# auxDaqUnitBottom2022.net
KiCad netlist of a schematic drawn in EAGLE
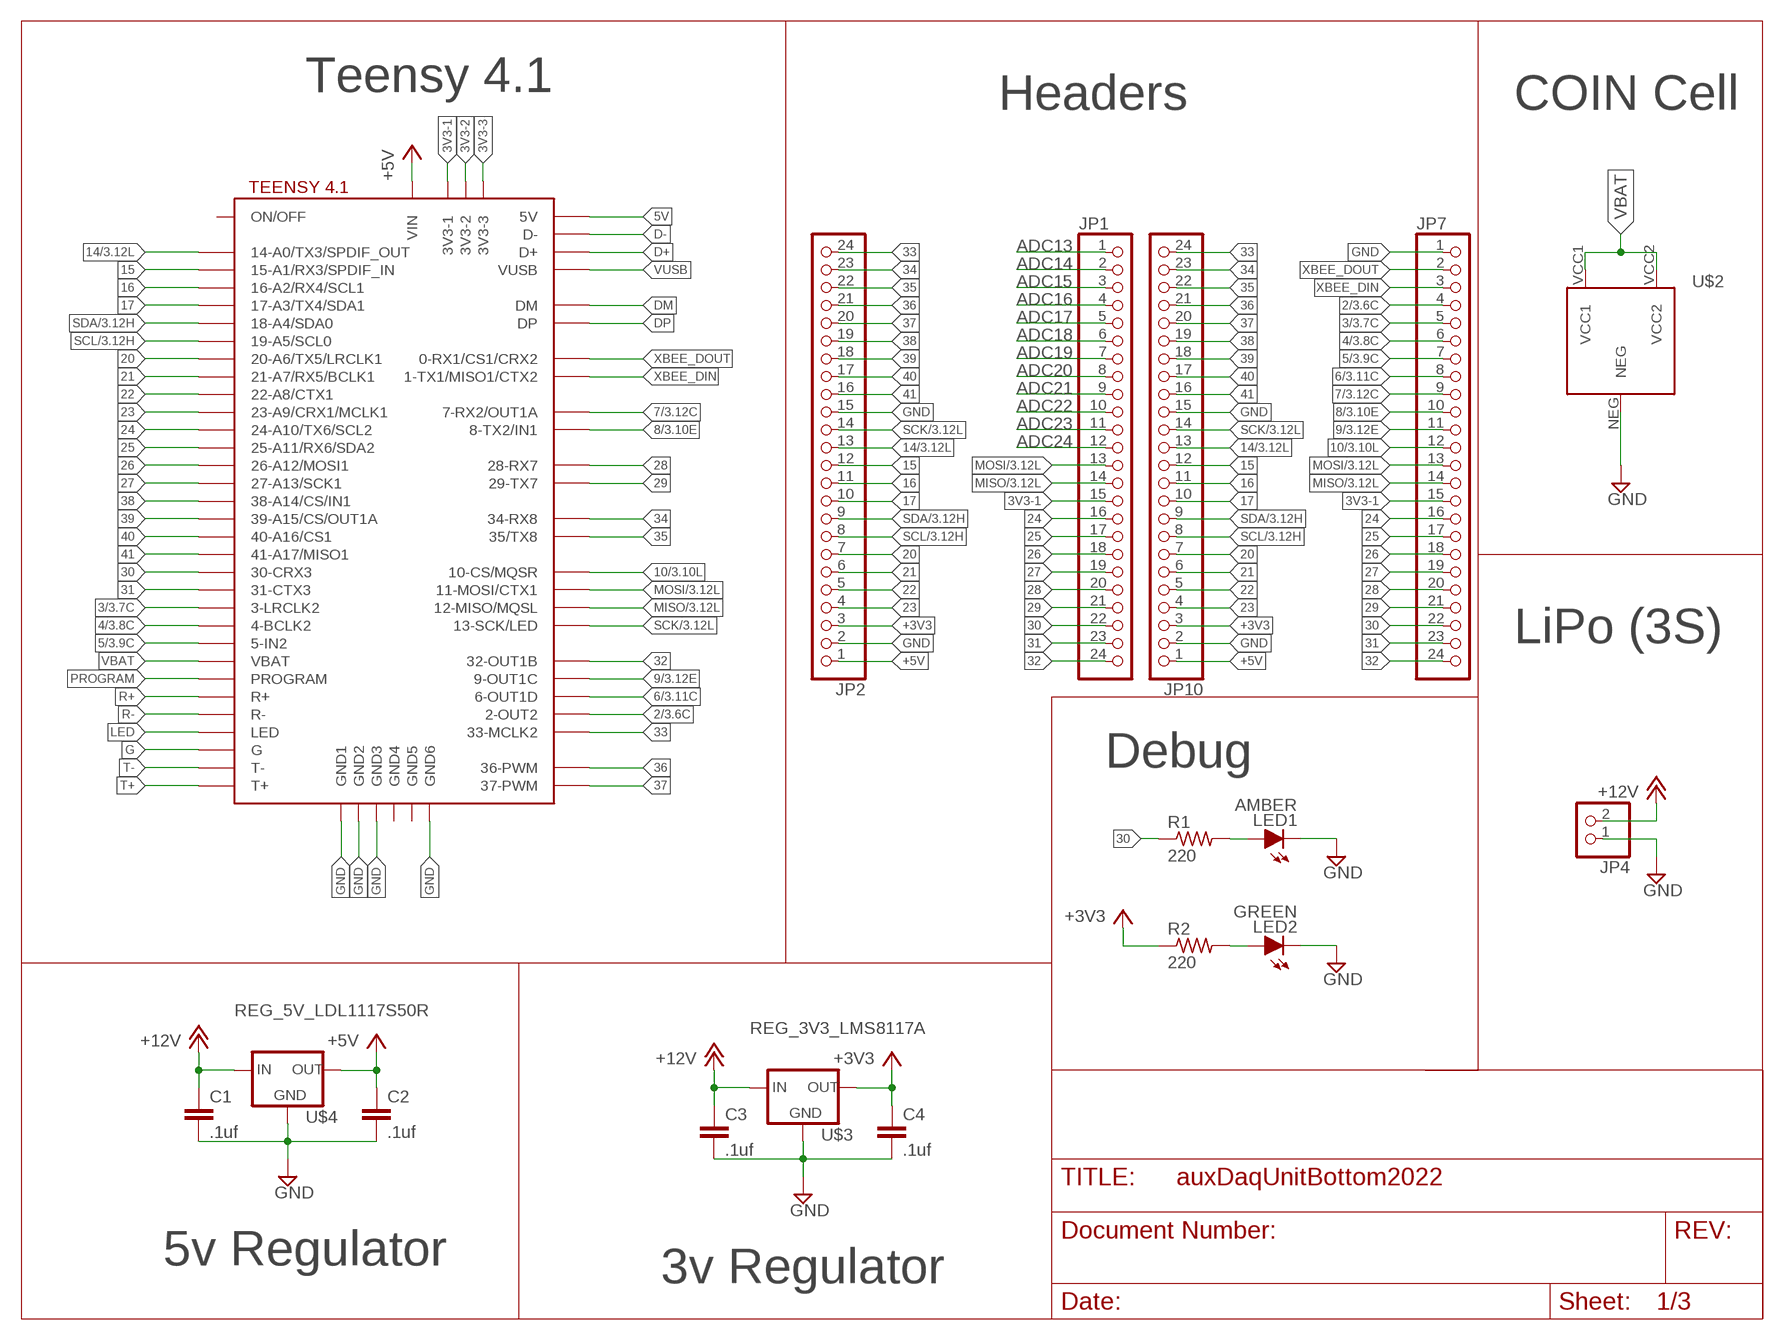
[diagram p0: schematic, sheet 1]
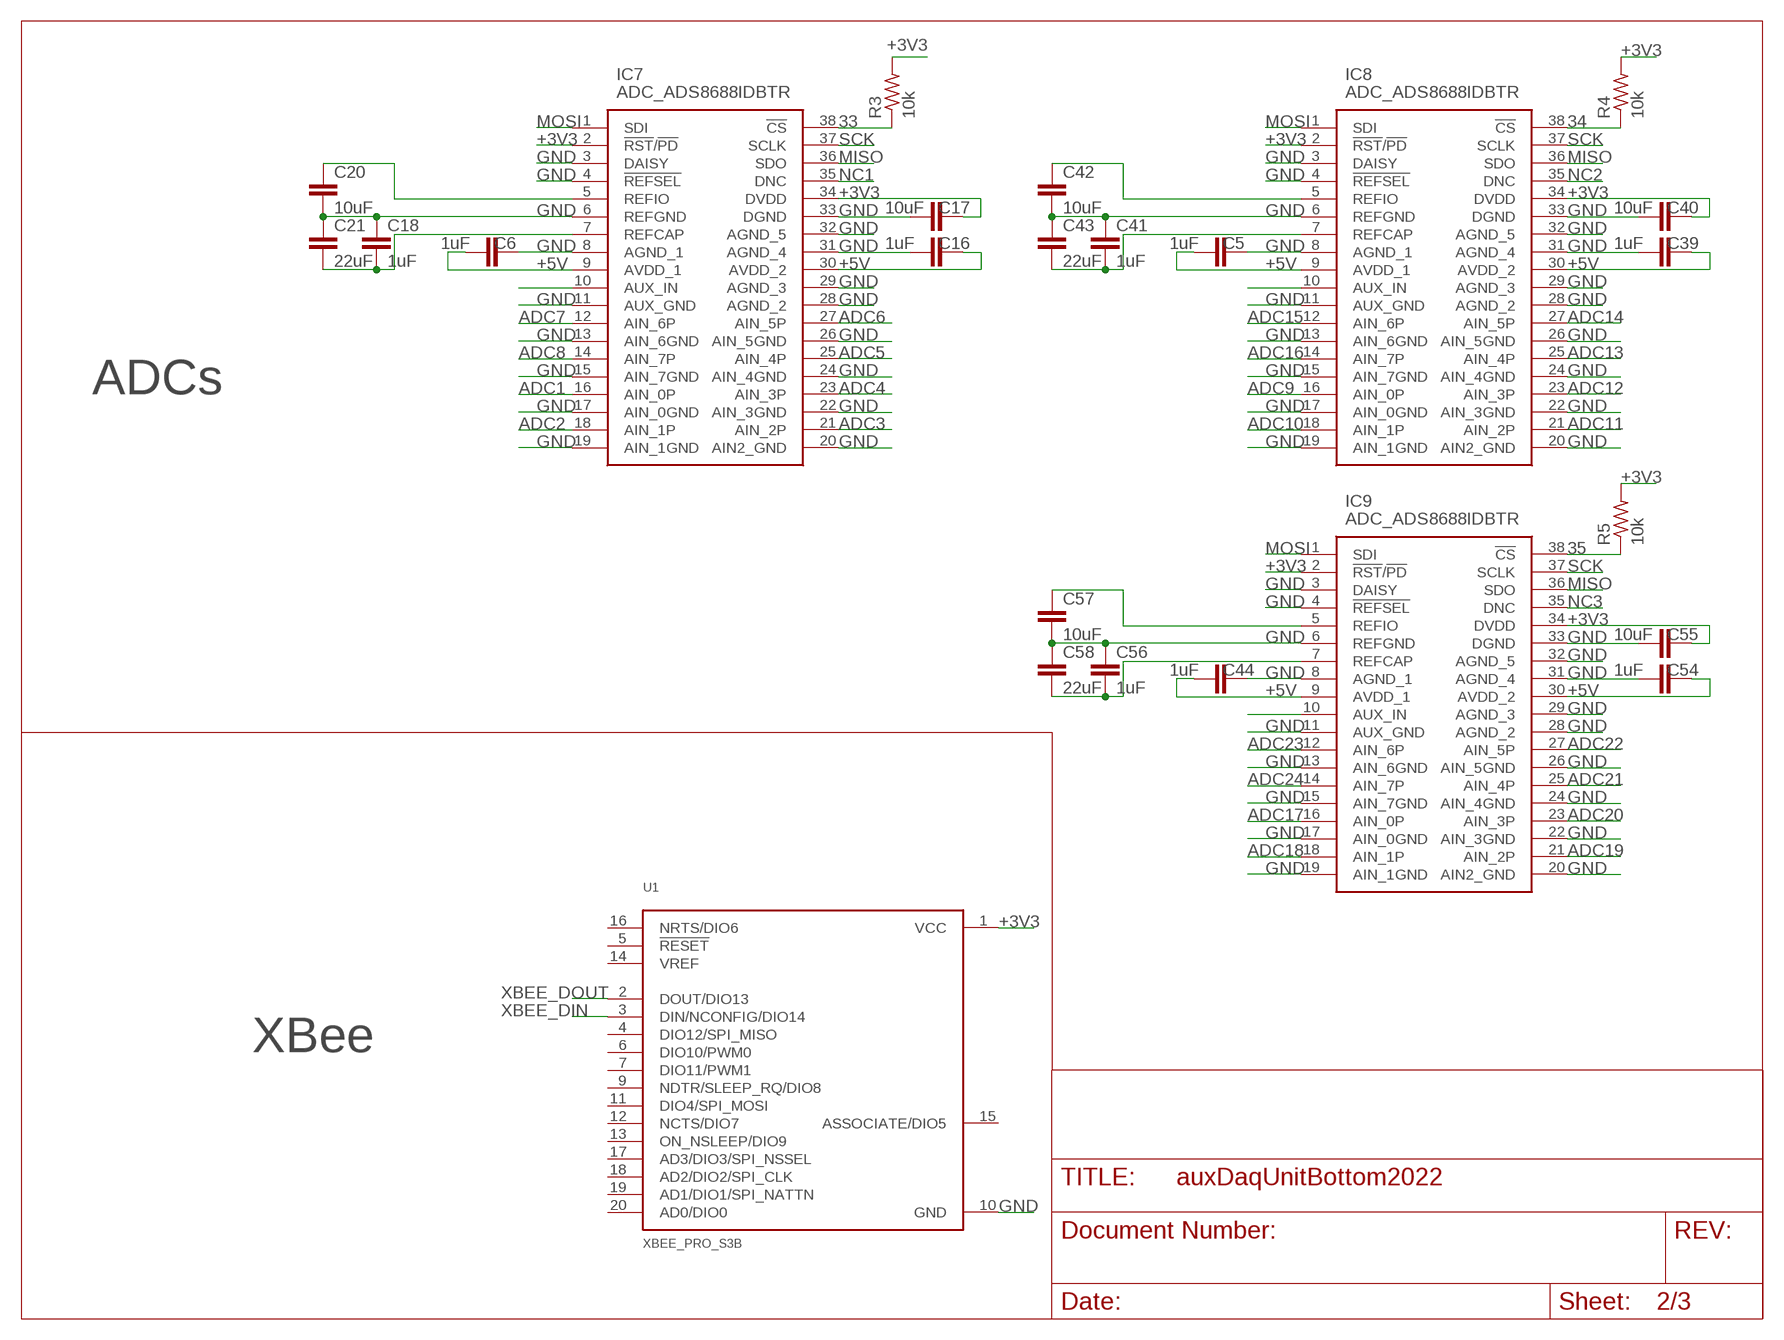
[diagram p1: schematic, sheet 2]
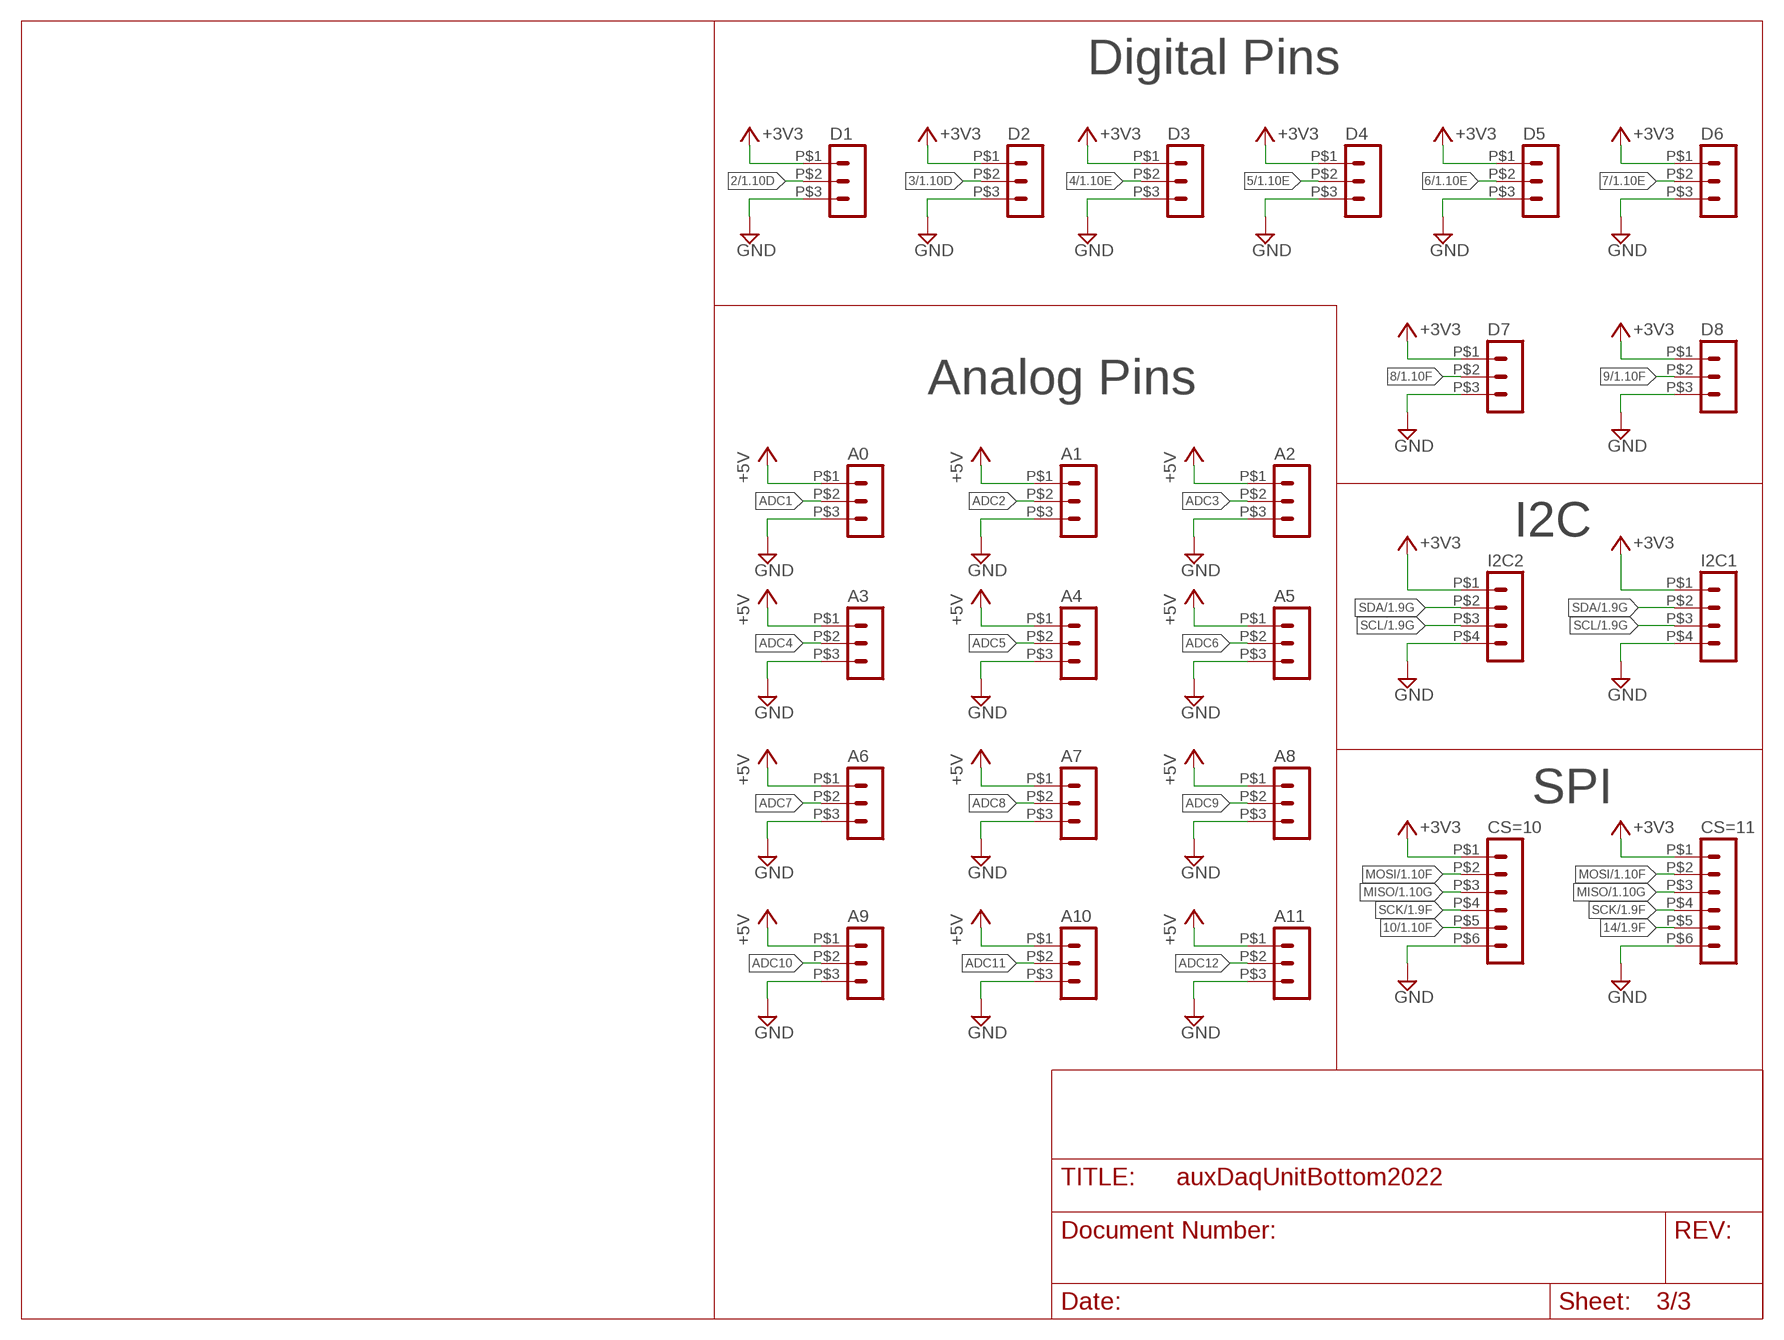
[diagram p2: schematic, sheet 3]

(export (version "E")
  (design (tool "Eeschema 10.0.6"))
  (components
    (comp (ref "C5")
      (value "1uF")
      (footprint "eagle-import:C0603")
      (libsource (lib "eagle-import") (part "CAP_SMDC0603"))
    )
    (comp (ref "C6")
      (value "1uF")
      (footprint "eagle-import:C0603")
      (libsource (lib "eagle-import") (part "CAP_SMDC0603"))
    )
    (comp (ref "C16")
      (value "1uF")
      (footprint "eagle-import:C0603")
      (libsource (lib "eagle-import") (part "CAP_SMDC0603"))
    )
    (comp (ref "C17")
      (value "10uF")
      (footprint "eagle-import:C0603")
      (libsource (lib "eagle-import") (part "CAP_SMDC0603"))
    )
    (comp (ref "C18")
      (value "1uF")
      (footprint "eagle-import:C0603")
      (libsource (lib "eagle-import") (part "CAP_SMDC0603"))
    )
    (comp (ref "C20")
      (value "10uF")
      (footprint "eagle-import:C0805")
      (libsource (lib "eagle-import") (part "CAP_SMDC0805"))
    )
    (comp (ref "C21")
      (value "22uF")
      (footprint "eagle-import:C1210")
      (libsource (lib "eagle-import") (part "CAP_SMDC1210"))
    )
    (comp (ref "C39")
      (value "1uF")
      (footprint "eagle-import:C0603")
      (libsource (lib "eagle-import") (part "CAP_SMDC0603"))
    )
    (comp (ref "C40")
      (value "10uF")
      (footprint "eagle-import:C0603")
      (libsource (lib "eagle-import") (part "CAP_SMDC0603"))
    )
    (comp (ref "C41")
      (value "1uF")
      (footprint "eagle-import:C0603")
      (libsource (lib "eagle-import") (part "CAP_SMDC0603"))
    )
    (comp (ref "C42")
      (value "10uF")
      (footprint "eagle-import:C0805")
      (libsource (lib "eagle-import") (part "CAP_SMDC0805"))
    )
    (comp (ref "C43")
      (value "22uF")
      (footprint "eagle-import:C1210")
      (libsource (lib "eagle-import") (part "CAP_SMDC1210"))
    )
    (comp (ref "C44")
      (value "1uF")
      (footprint "eagle-import:C0603")
      (libsource (lib "eagle-import") (part "CAP_SMDC0603"))
    )
    (comp (ref "C54")
      (value "1uF")
      (footprint "eagle-import:C0603")
      (libsource (lib "eagle-import") (part "CAP_SMDC0603"))
    )
    (comp (ref "C55")
      (value "10uF")
      (footprint "eagle-import:C0603")
      (libsource (lib "eagle-import") (part "CAP_SMDC0603"))
    )
    (comp (ref "C56")
      (value "1uF")
      (footprint "eagle-import:C0603")
      (libsource (lib "eagle-import") (part "CAP_SMDC0603"))
    )
    (comp (ref "C57")
      (value "10uF")
      (footprint "eagle-import:C0805")
      (libsource (lib "eagle-import") (part "CAP_SMDC0805"))
    )
    (comp (ref "C58")
      (value "22uF")
      (footprint "eagle-import:C1210")
      (libsource (lib "eagle-import") (part "CAP_SMDC1210"))
    )
    (comp (ref "IC7")
      (value "ADC_ADS8688IDBTR")
      (footprint "eagle-import:SOP50P640X120-38N")
      (fields
        (field (name "ARROW_PART_NUMBER") "ADS8688IDBTR")
        (field (name "MOUSER_PART_NUMBER") "595-ADS8688IDBTR")
      )
      (libsource (lib "eagle-import") (part "ADC_ADS8688IDBTR"))
    )
    (comp (ref "IC8")
      (value "ADC_ADS8688IDBTR")
      (footprint "eagle-import:SOP50P640X120-38N")
      (fields
        (field (name "ARROW_PART_NUMBER") "ADS8688IDBTR")
        (field (name "MOUSER_PART_NUMBER") "595-ADS8688IDBTR")
      )
      (libsource (lib "eagle-import") (part "ADC_ADS8688IDBTR"))
    )
    (comp (ref "IC9")
      (value "ADC_ADS8688IDBTR")
      (footprint "eagle-import:SOP50P640X120-38N")
      (fields
        (field (name "ARROW_PART_NUMBER") "ADS8688IDBTR")
        (field (name "MOUSER_PART_NUMBER") "595-ADS8688IDBTR")
      )
      (libsource (lib "eagle-import") (part "ADC_ADS8688IDBTR"))
    )
    (comp (ref "R3")
      (value "10k")
      (footprint "eagle-import:R0603")
      (libsource (lib "eagle-import") (part "RES_SMDR0603"))
    )
    (comp (ref "R4")
      (value "10k")
      (footprint "eagle-import:R0603")
      (libsource (lib "eagle-import") (part "RES_SMDR0603"))
    )
    (comp (ref "R5")
      (value "10k")
      (footprint "eagle-import:R0603")
      (libsource (lib "eagle-import") (part "RES_SMDR0603"))
    )
    (comp (ref "U1")
      (value "XBEE_PRO_S3B")
      (footprint "eagle-import:XBEE_PRO_S3B")
      (fields
        (field (name "DIGI-KEY_PART_NUMBER") "602-1293-ND")
        (field (name "MF") "Digi International")
        (field (name "MP") "XBP9B-XCST-001")
      )
      (libsource (lib "eagle-import") (part "XBEE_PRO_S3B"))
    )
    (comp (ref "A0")
      (value "HEADER_POS3_43650-0300")
      (footprint "eagle-import:43650-0300")
      (libsource (lib "eagle-import") (part "HEADER_POS3_?43650-0300"))
    )
    (comp (ref "A1")
      (value "HEADER_POS3_43650-0300")
      (footprint "eagle-import:43650-0300")
      (libsource (lib "eagle-import") (part "HEADER_POS3_?43650-0300"))
    )
    (comp (ref "A2")
      (value "HEADER_POS3_43650-0300")
      (footprint "eagle-import:43650-0300")
      (libsource (lib "eagle-import") (part "HEADER_POS3_?43650-0300"))
    )
    (comp (ref "A3")
      (value "HEADER_POS3_43650-0300")
      (footprint "eagle-import:43650-0300")
      (libsource (lib "eagle-import") (part "HEADER_POS3_?43650-0300"))
    )
    (comp (ref "A4")
      (value "HEADER_POS3_43650-0300")
      (footprint "eagle-import:43650-0300")
      (libsource (lib "eagle-import") (part "HEADER_POS3_?43650-0300"))
    )
    (comp (ref "A5")
      (value "HEADER_POS3_43650-0300")
      (footprint "eagle-import:43650-0300")
      (libsource (lib "eagle-import") (part "HEADER_POS3_?43650-0300"))
    )
    (comp (ref "A6")
      (value "HEADER_POS3_43650-0300")
      (footprint "eagle-import:43650-0300")
      (libsource (lib "eagle-import") (part "HEADER_POS3_?43650-0300"))
    )
    (comp (ref "A7")
      (value "HEADER_POS3_43650-0300")
      (footprint "eagle-import:43650-0300")
      (libsource (lib "eagle-import") (part "HEADER_POS3_?43650-0300"))
    )
    (comp (ref "A8")
      (value "HEADER_POS3_43650-0300")
      (footprint "eagle-import:43650-0300")
      (libsource (lib "eagle-import") (part "HEADER_POS3_?43650-0300"))
    )
    (comp (ref "A9")
      (value "HEADER_POS3_43650-0300")
      (footprint "eagle-import:43650-0300")
      (libsource (lib "eagle-import") (part "HEADER_POS3_?43650-0300"))
    )
    (comp (ref "A10")
      (value "HEADER_POS3_43650-0300")
      (footprint "eagle-import:43650-0300")
      (libsource (lib "eagle-import") (part "HEADER_POS3_?43650-0300"))
    )
    (comp (ref "A11")
      (value "HEADER_POS3_43650-0300")
      (footprint "eagle-import:43650-0300")
      (libsource (lib "eagle-import") (part "HEADER_POS3_?43650-0300"))
    )
    (comp (ref "CS=10")
      (value "HEADER_POS6_43045-0600")
      (footprint "eagle-import:43045-0600")
      (libsource (lib "eagle-import") (part "HEADER_POS6_?43045-0600"))
    )
    (comp (ref "CS=11")
      (value "HEADER_POS6_43045-0600")
      (footprint "eagle-import:43045-0600")
      (libsource (lib "eagle-import") (part "HEADER_POS6_?43045-0600"))
    )
    (comp (ref "D1")
      (value "HEADER_POS3_43650-0300")
      (footprint "eagle-import:43650-0300")
      (libsource (lib "eagle-import") (part "HEADER_POS3_?43650-0300"))
    )
    (comp (ref "D2")
      (value "HEADER_POS3_43650-0300")
      (footprint "eagle-import:43650-0300")
      (libsource (lib "eagle-import") (part "HEADER_POS3_?43650-0300"))
    )
    (comp (ref "D3")
      (value "HEADER_POS3_43650-0300")
      (footprint "eagle-import:43650-0300")
      (libsource (lib "eagle-import") (part "HEADER_POS3_?43650-0300"))
    )
    (comp (ref "D4")
      (value "HEADER_POS3_43650-0300")
      (footprint "eagle-import:43650-0300")
      (libsource (lib "eagle-import") (part "HEADER_POS3_?43650-0300"))
    )
    (comp (ref "D5")
      (value "HEADER_POS3_43650-0300")
      (footprint "eagle-import:43650-0300")
      (libsource (lib "eagle-import") (part "HEADER_POS3_?43650-0300"))
    )
    (comp (ref "D6")
      (value "HEADER_POS3_43650-0300")
      (footprint "eagle-import:43650-0300")
      (libsource (lib "eagle-import") (part "HEADER_POS3_?43650-0300"))
    )
    (comp (ref "D7")
      (value "HEADER_POS3_43650-0300")
      (footprint "eagle-import:43650-0300")
      (libsource (lib "eagle-import") (part "HEADER_POS3_?43650-0300"))
    )
    (comp (ref "D8")
      (value "HEADER_POS3_43650-0300")
      (footprint "eagle-import:43650-0300")
      (libsource (lib "eagle-import") (part "HEADER_POS3_?43650-0300"))
    )
    (comp (ref "I2C1")
      (value "HEADER_POS4_43045-0401")
      (footprint "eagle-import:43045-0400")
      (libsource (lib "eagle-import") (part "HEADER_POS4_?43045-0401"))
    )
    (comp (ref "I2C2")
      (value "HEADER_POS4_43045-0401")
      (footprint "eagle-import:43045-0400")
      (libsource (lib "eagle-import") (part "HEADER_POS4_?43045-0401"))
    )
    (comp (ref "C1")
      (value ".1uf")
      (footprint "eagle-import:C0603")
      (libsource (lib "eagle-import") (part "CAP_SMDC0603"))
    )
    (comp (ref "C2")
      (value ".1uf")
      (footprint "eagle-import:C0603")
      (libsource (lib "eagle-import") (part "CAP_SMDC0603"))
    )
    (comp (ref "C3")
      (value ".1uf")
      (footprint "eagle-import:C0603")
      (libsource (lib "eagle-import") (part "CAP_SMDC0603"))
    )
    (comp (ref "C4")
      (value ".1uf")
      (footprint "eagle-import:C0603")
      (libsource (lib "eagle-import") (part "CAP_SMDC0603"))
    )
    (comp (ref "JP1")
      (value "PINHD-1X24")
      (footprint "eagle-import:1X24")
      (libsource (lib "eagle-import") (part "PINHD-1X24"))
    )
    (comp (ref "JP2")
      (value "PINHD-1X24")
      (footprint "eagle-import:1X24")
      (libsource (lib "eagle-import") (part "PINHD-1X24"))
    )
    (comp (ref "JP4")
      (value "PINHD-1X2")
      (footprint "eagle-import:1X02")
      (libsource (lib "eagle-import") (part "PINHD-1X2"))
    )
    (comp (ref "JP7")
      (value "PINHD-1X24")
      (footprint "eagle-import:1X24")
      (libsource (lib "eagle-import") (part "PINHD-1X24"))
    )
    (comp (ref "JP10")
      (value "PINHD-1X24")
      (footprint "eagle-import:1X24")
      (libsource (lib "eagle-import") (part "PINHD-1X24"))
    )
    (comp (ref "LED1")
      (value "AMBER")
      (footprint "eagle-import:LED-603")
      (libsource (lib "eagle-import") (part "LED-0603"))
    )
    (comp (ref "LED2")
      (value "GREEN")
      (footprint "eagle-import:LED-603")
      (libsource (lib "eagle-import") (part "LED-0603"))
    )
    (comp (ref "R1")
      (value "220")
      (footprint "eagle-import:R0603")
      (libsource (lib "eagle-import") (part "RES_SMDR0603"))
    )
    (comp (ref "R2")
      (value "220")
      (footprint "eagle-import:R0603")
      (libsource (lib "eagle-import") (part "RES_SMDR0603"))
    )
    (comp (ref "U$1")
      (value "TEENSY41")
      (footprint "eagle-import:TEENSY41")
      (libsource (lib "eagle-import") (part "TEENSY41"))
    )
    (comp (ref "U$2")
      (value "KEYSTONE3035")
      (footprint "eagle-import:KEYSTONE3035")
      (libsource (lib "eagle-import") (part "KEYSTONE3035"))
    )
    (comp (ref "U$3")
      (value "REG_3V3_LMS8117A")
      (footprint "eagle-import:SOT223")
      (libsource (lib "eagle-import") (part "REG_3V3_LMS8117A"))
    )
    (comp (ref "U$4")
      (value "REG_5V_LDL1117S50R")
      (footprint "eagle-import:SOT230P700X180-4N")
      (libsource (lib "eagle-import") (part "REG_5V_LDL1117S50R"))
    )
  )
  (nets
    (net (code "1") (name "+3V3") (class "Default")
      (node (ref "C17") (pin "1") (pinfunction "1_1") (pintype "passive"))
      (node (ref "C4") (pin "1") (pinfunction "1_1") (pintype "passive"))
      (node (ref "C40") (pin "1") (pinfunction "1_1") (pintype "passive"))
      (node (ref "C55") (pin "1") (pinfunction "1_1") (pintype "passive"))
      (node (ref "CS=10") (pin "P$1") (pinfunction "1_P$1") (pintype "passive"))
      (node (ref "CS=11") (pin "P$1") (pinfunction "1_P$1") (pintype "passive"))
      (node (ref "D1") (pin "P$1") (pinfunction "1_P$1") (pintype "passive"))
      (node (ref "D2") (pin "P$1") (pinfunction "1_P$1") (pintype "passive"))
      (node (ref "D3") (pin "P$1") (pinfunction "1_P$1") (pintype "passive"))
      (node (ref "D4") (pin "P$1") (pinfunction "1_P$1") (pintype "passive"))
      (node (ref "D5") (pin "P$1") (pinfunction "1_P$1") (pintype "passive"))
      (node (ref "D6") (pin "P$1") (pinfunction "1_P$1") (pintype "passive"))
      (node (ref "D7") (pin "P$1") (pinfunction "1_P$1") (pintype "passive"))
      (node (ref "D8") (pin "P$1") (pinfunction "1_P$1") (pintype "passive"))
      (node (ref "I2C1") (pin "P$1") (pinfunction "1_P$1") (pintype "passive"))
      (node (ref "I2C2") (pin "P$1") (pinfunction "1_P$1") (pintype "passive"))
      (node (ref "IC7") (pin "2") (pinfunction "~{RST}/~{PD}_2") (pintype "bidirectional"))
      (node (ref "IC7") (pin "34") (pinfunction "DVDD_34") (pintype "bidirectional"))
      (node (ref "IC8") (pin "2") (pinfunction "~{RST}/~{PD}_2") (pintype "bidirectional"))
      (node (ref "IC8") (pin "34") (pinfunction "DVDD_34") (pintype "bidirectional"))
      (node (ref "IC9") (pin "2") (pinfunction "~{RST}/~{PD}_2") (pintype "bidirectional"))
      (node (ref "IC9") (pin "34") (pinfunction "DVDD_34") (pintype "bidirectional"))
      (node (ref "JP10") (pin "3") (pinfunction "3_3") (pintype "passive"))
      (node (ref "JP2") (pin "3") (pinfunction "3_3") (pintype "passive"))
      (node (ref "R2") (pin "1") (pinfunction "1_1") (pintype "passive"))
      (node (ref "R3") (pin "2") (pinfunction "2_2") (pintype "passive"))
      (node (ref "R4") (pin "2") (pinfunction "2_2") (pintype "passive"))
      (node (ref "R5") (pin "2") (pinfunction "2_2") (pintype "passive"))
      (node (ref "U$3") (pin "2") (pinfunction "OUT_2") (pintype "output"))
      (node (ref "U$3") (pin "4") (pinfunction "OUT_4") (pintype "output"))
      (node (ref "U1") (pin "1") (pinfunction "VCC_1") (pintype "power_in"))
    )
    (net (code "2") (name "+5V") (class "Default")
      (node (ref "A0") (pin "P$1") (pinfunction "1_P$1") (pintype "passive"))
      (node (ref "A1") (pin "P$1") (pinfunction "1_P$1") (pintype "passive"))
      (node (ref "A10") (pin "P$1") (pinfunction "1_P$1") (pintype "passive"))
      (node (ref "A11") (pin "P$1") (pinfunction "1_P$1") (pintype "passive"))
      (node (ref "A2") (pin "P$1") (pinfunction "1_P$1") (pintype "passive"))
      (node (ref "A3") (pin "P$1") (pinfunction "1_P$1") (pintype "passive"))
      (node (ref "A4") (pin "P$1") (pinfunction "1_P$1") (pintype "passive"))
      (node (ref "A5") (pin "P$1") (pinfunction "1_P$1") (pintype "passive"))
      (node (ref "A6") (pin "P$1") (pinfunction "1_P$1") (pintype "passive"))
      (node (ref "A7") (pin "P$1") (pinfunction "1_P$1") (pintype "passive"))
      (node (ref "A8") (pin "P$1") (pinfunction "1_P$1") (pintype "passive"))
      (node (ref "A9") (pin "P$1") (pinfunction "1_P$1") (pintype "passive"))
      (node (ref "C16") (pin "1") (pinfunction "1_1") (pintype "passive"))
      (node (ref "C2") (pin "1") (pinfunction "1_1") (pintype "passive"))
      (node (ref "C39") (pin "1") (pinfunction "1_1") (pintype "passive"))
      (node (ref "C44") (pin "2") (pinfunction "2_2") (pintype "passive"))
      (node (ref "C5") (pin "2") (pinfunction "2_2") (pintype "passive"))
      (node (ref "C54") (pin "1") (pinfunction "1_1") (pintype "passive"))
      (node (ref "C6") (pin "2") (pinfunction "2_2") (pintype "passive"))
      (node (ref "IC7") (pin "30") (pinfunction "AVDD_2_30") (pintype "bidirectional"))
      (node (ref "IC7") (pin "9") (pinfunction "AVDD_1_9") (pintype "bidirectional"))
      (node (ref "IC8") (pin "30") (pinfunction "AVDD_2_30") (pintype "bidirectional"))
      (node (ref "IC8") (pin "9") (pinfunction "AVDD_1_9") (pintype "bidirectional"))
      (node (ref "IC9") (pin "30") (pinfunction "AVDD_2_30") (pintype "bidirectional"))
      (node (ref "IC9") (pin "9") (pinfunction "AVDD_1_9") (pintype "bidirectional"))
      (node (ref "JP10") (pin "1") (pinfunction "1_1") (pintype "passive"))
      (node (ref "JP2") (pin "1") (pinfunction "1_1") (pintype "passive"))
      (node (ref "U$1") (pin "VIN") (pinfunction "VIN_VIN") (pintype "bidirectional"))
      (node (ref "U$4") (pin "2") (pinfunction "OUT_2") (pintype "output"))
      (node (ref "U$4") (pin "4") (pinfunction "OUT_4") (pintype "output"))
    )
    (net (code "3") (name "+12V") (class "Default")
      (node (ref "C1") (pin "1") (pinfunction "1_1") (pintype "passive"))
      (node (ref "C3") (pin "1") (pinfunction "1_1") (pintype "passive"))
      (node (ref "JP4") (pin "2") (pinfunction "2_2") (pintype "passive"))
      (node (ref "U$3") (pin "3") (pinfunction "IN_3") (pintype "input"))
      (node (ref "U$4") (pin "3") (pinfunction "IN_3") (pintype "input"))
    )
    (net (code "4") (name "2") (class "Default")
      (node (ref "D1") (pin "P$2") (pinfunction "2_P$2") (pintype "passive"))
      (node (ref "JP7") (pin "4") (pinfunction "4_4") (pintype "passive"))
      (node (ref "U$1") (pin "2-OUT2") (pinfunction "2-OUT2_2-OUT2") (pintype "bidirectional"))
    )
    (net (code "5") (name "3") (class "Default")
      (node (ref "D2") (pin "P$2") (pinfunction "2_P$2") (pintype "passive"))
      (node (ref "JP7") (pin "5") (pinfunction "5_5") (pintype "passive"))
      (node (ref "U$1") (pin "3-LRCLK2") (pinfunction "3-LRCLK2_3-LRCLK2") (pintype "bidirectional"))
    )
    (net (code "6") (name "3V3-1") (class "Default")
      (node (ref "JP1") (pin "15") (pinfunction "15_15") (pintype "passive"))
      (node (ref "JP7") (pin "15") (pinfunction "15_15") (pintype "passive"))
      (node (ref "U$1") (pin "3V3-1") (pinfunction "3V3-1_3V3-1") (pintype "bidirectional"))
    )
    (net (code "7") (name "3V3-2") (class "Default")
      (node (ref "U$1") (pin "3V3-2") (pinfunction "3V3-2_3V3-2") (pintype "bidirectional"))
    )
    (net (code "8") (name "3V3-3") (class "Default")
      (node (ref "U$1") (pin "3V3-3") (pinfunction "3V3-3_3V3-3") (pintype "bidirectional"))
    )
    (net (code "9") (name "4") (class "Default")
      (node (ref "D3") (pin "P$2") (pinfunction "2_P$2") (pintype "passive"))
      (node (ref "JP7") (pin "6") (pinfunction "6_6") (pintype "passive"))
      (node (ref "U$1") (pin "4-BCLK2") (pinfunction "4-BCLK2_4-BCLK2") (pintype "bidirectional"))
    )
    (net (code "10") (name "5") (class "Default")
      (node (ref "D4") (pin "P$2") (pinfunction "2_P$2") (pintype "passive"))
      (node (ref "JP7") (pin "7") (pinfunction "7_7") (pintype "passive"))
      (node (ref "U$1") (pin "5-IN2") (pinfunction "5-IN2_5-IN2") (pintype "bidirectional"))
    )
    (net (code "11") (name "5V") (class "Default")
      (node (ref "U$1") (pin "+5V") (pinfunction "5V_+5V") (pintype "bidirectional"))
    )
    (net (code "12") (name "6") (class "Default")
      (node (ref "D5") (pin "P$2") (pinfunction "2_P$2") (pintype "passive"))
      (node (ref "JP7") (pin "8") (pinfunction "8_8") (pintype "passive"))
      (node (ref "U$1") (pin "6-OUT1D") (pinfunction "6-OUT1D_6-OUT1D") (pintype "bidirectional"))
    )
    (net (code "13") (name "7") (class "Default")
      (node (ref "D6") (pin "P$2") (pinfunction "2_P$2") (pintype "passive"))
      (node (ref "JP7") (pin "9") (pinfunction "9_9") (pintype "passive"))
      (node (ref "U$1") (pin "7-RX2/OUT1A") (pinfunction "7-RX2/OUT1A_7-RX2/OUT1A") (pintype "bidirectional"))
    )
    (net (code "14") (name "8") (class "Default")
      (node (ref "D7") (pin "P$2") (pinfunction "2_P$2") (pintype "passive"))
      (node (ref "JP7") (pin "10") (pinfunction "10_10") (pintype "passive"))
      (node (ref "U$1") (pin "8-TX2/IN2") (pinfunction "8-TX2/IN1_8-TX2/IN2") (pintype "bidirectional"))
    )
    (net (code "15") (name "9") (class "Default")
      (node (ref "D8") (pin "P$2") (pinfunction "2_P$2") (pintype "passive"))
      (node (ref "JP7") (pin "11") (pinfunction "11_11") (pintype "passive"))
      (node (ref "U$1") (pin "9-OUT1C") (pinfunction "9-OUT1C_9-OUT1C") (pintype "bidirectional"))
    )
    (net (code "16") (name "10") (class "Default")
      (node (ref "CS=10") (pin "P$5") (pinfunction "5_P$5") (pintype "passive"))
      (node (ref "JP7") (pin "12") (pinfunction "12_12") (pintype "passive"))
      (node (ref "U$1") (pin "10-CS\\MQSR") (pinfunction "10-CS/MQSR_10-CS\\MQSR") (pintype "bidirectional"))
    )
    (net (code "17") (name "14") (class "Default")
      (node (ref "CS=11") (pin "P$5") (pinfunction "5_P$5") (pintype "passive"))
      (node (ref "JP10") (pin "13") (pinfunction "13_13") (pintype "passive"))
      (node (ref "JP2") (pin "13") (pinfunction "13_13") (pintype "passive"))
      (node (ref "U$1") (pin "14-A0/TX3/SPDIF_OUT") (pinfunction "14-A0/TX3/SPDIF_OUT_14-A0/TX3/SPDIF_OUT") (pintype "bidirectional"))
    )
    (net (code "18") (name "15") (class "Default")
      (node (ref "JP10") (pin "12") (pinfunction "12_12") (pintype "passive"))
      (node (ref "JP2") (pin "12") (pinfunction "12_12") (pintype "passive"))
      (node (ref "U$1") (pin "15-A1/RX3/SPDIF_IN") (pinfunction "15-A1/RX3/SPDIF_IN_15-A1/RX3/SPDIF_IN") (pintype "bidirectional"))
    )
    (net (code "19") (name "16") (class "Default")
      (node (ref "JP10") (pin "11") (pinfunction "11_11") (pintype "passive"))
      (node (ref "JP2") (pin "11") (pinfunction "11_11") (pintype "passive"))
      (node (ref "U$1") (pin "16-A2/RX4/SCL1") (pinfunction "16-A2/RX4/SCL1_16-A2/RX4/SCL1") (pintype "bidirectional"))
    )
    (net (code "20") (name "17") (class "Default")
      (node (ref "JP10") (pin "10") (pinfunction "10_10") (pintype "passive"))
      (node (ref "JP2") (pin "10") (pinfunction "10_10") (pintype "passive"))
      (node (ref "U$1") (pin "17-A3/TX4/SDA1") (pinfunction "17-A3/TX4/SDA1_17-A3/TX4/SDA1") (pintype "bidirectional"))
    )
    (net (code "21") (name "20") (class "Default")
      (node (ref "JP10") (pin "7") (pinfunction "7_7") (pintype "passive"))
      (node (ref "JP2") (pin "7") (pinfunction "7_7") (pintype "passive"))
      (node (ref "U$1") (pin "20-A6/TX5/LRCLK1") (pinfunction "20-A6/TX5/LRCLK1_20-A6/TX5/LRCLK1") (pintype "bidirectional"))
    )
    (net (code "22") (name "21") (class "Default")
      (node (ref "JP10") (pin "6") (pinfunction "6_6") (pintype "passive"))
      (node (ref "JP2") (pin "6") (pinfunction "6_6") (pintype "passive"))
      (node (ref "U$1") (pin "21-A7/RX5/BCLK1") (pinfunction "21-A7/RX5/BCLK1_21-A7/RX5/BCLK1") (pintype "bidirectional"))
    )
    (net (code "23") (name "22") (class "Default")
      (node (ref "JP10") (pin "5") (pinfunction "5_5") (pintype "passive"))
      (node (ref "JP2") (pin "5") (pinfunction "5_5") (pintype "passive"))
      (node (ref "U$1") (pin "22-A8/CTX1") (pinfunction "22-A8/CTX1_22-A8/CTX1") (pintype "bidirectional"))
    )
    (net (code "24") (name "23") (class "Default")
      (node (ref "JP10") (pin "4") (pinfunction "4_4") (pintype "passive"))
      (node (ref "JP2") (pin "4") (pinfunction "4_4") (pintype "passive"))
      (node (ref "U$1") (pin "23-A9/CRX1/MCLK1") (pinfunction "23-A9/CRX1/MCLK1_23-A9/CRX1/MCLK1") (pintype "bidirectional"))
    )
    (net (code "25") (name "24") (class "Default")
      (node (ref "JP1") (pin "16") (pinfunction "16_16") (pintype "passive"))
      (node (ref "JP7") (pin "16") (pinfunction "16_16") (pintype "passive"))
      (node (ref "U$1") (pin "24-A10/TX6/SCL2") (pinfunction "24-A10/TX6/SCL2_24-A10/TX6/SCL2") (pintype "bidirectional"))
    )
    (net (code "26") (name "25") (class "Default")
      (node (ref "JP1") (pin "17") (pinfunction "17_17") (pintype "passive"))
      (node (ref "JP7") (pin "17") (pinfunction "17_17") (pintype "passive"))
      (node (ref "U$1") (pin "25-A11/RX6/SDA2") (pinfunction "25-A11/RX6/SDA2_25-A11/RX6/SDA2") (pintype "bidirectional"))
    )
    (net (code "27") (name "26") (class "Default")
      (node (ref "JP1") (pin "18") (pinfunction "18_18") (pintype "passive"))
      (node (ref "JP7") (pin "18") (pinfunction "18_18") (pintype "passive"))
      (node (ref "U$1") (pin "26-A12/MOSI1") (pinfunction "26-A12/MOSI1_26-A12/MOSI1") (pintype "bidirectional"))
    )
    (net (code "28") (name "27") (class "Default")
      (node (ref "JP1") (pin "19") (pinfunction "19_19") (pintype "passive"))
      (node (ref "JP7") (pin "19") (pinfunction "19_19") (pintype "passive"))
      (node (ref "U$1") (pin "27-A13/SCK1") (pinfunction "27-A13/SCK1_27-A13/SCK1") (pintype "bidirectional"))
    )
    (net (code "29") (name "28") (class "Default")
      (node (ref "JP1") (pin "20") (pinfunction "20_20") (pintype "passive"))
      (node (ref "JP7") (pin "20") (pinfunction "20_20") (pintype "passive"))
      (node (ref "U$1") (pin "28-RX7") (pinfunction "28-RX7_28-RX7") (pintype "bidirectional"))
    )
    (net (code "30") (name "29") (class "Default")
      (node (ref "JP1") (pin "21") (pinfunction "21_21") (pintype "passive"))
      (node (ref "JP7") (pin "21") (pinfunction "21_21") (pintype "passive"))
      (node (ref "U$1") (pin "29-TX7") (pinfunction "29-TX7_29-TX7") (pintype "bidirectional"))
    )
    (net (code "31") (name "30") (class "Default")
      (node (ref "JP1") (pin "22") (pinfunction "22_22") (pintype "passive"))
      (node (ref "JP7") (pin "22") (pinfunction "22_22") (pintype "passive"))
      (node (ref "R1") (pin "1") (pinfunction "1_1") (pintype "passive"))
      (node (ref "U$1") (pin "30-CRX3") (pinfunction "30-CRX3_30-CRX3") (pintype "bidirectional"))
    )
    (net (code "32") (name "31") (class "Default")
      (node (ref "JP1") (pin "23") (pinfunction "23_23") (pintype "passive"))
      (node (ref "JP7") (pin "23") (pinfunction "23_23") (pintype "passive"))
      (node (ref "U$1") (pin "31-CTX3") (pinfunction "31-CTX3_31-CTX3") (pintype "bidirectional"))
    )
    (net (code "33") (name "32") (class "Default")
      (node (ref "JP1") (pin "24") (pinfunction "24_24") (pintype "passive"))
      (node (ref "JP7") (pin "24") (pinfunction "24_24") (pintype "passive"))
      (node (ref "U$1") (pin "32-OUT1B") (pinfunction "32-OUT1B_32-OUT1B") (pintype "bidirectional"))
    )
    (net (code "34") (name "33") (class "Default")
      (node (ref "IC7") (pin "38") (pinfunction "~{CS}_38") (pintype "bidirectional"))
      (node (ref "JP10") (pin "24") (pinfunction "24_24") (pintype "passive"))
      (node (ref "JP2") (pin "24") (pinfunction "24_24") (pintype "passive"))
      (node (ref "R3") (pin "1") (pinfunction "1_1") (pintype "passive"))
      (node (ref "U$1") (pin "33-MCLK2") (pinfunction "33-MCLK2_33-MCLK2") (pintype "bidirectional"))
    )
    (net (code "35") (name "34") (class "Default")
      (node (ref "IC8") (pin "38") (pinfunction "~{CS}_38") (pintype "bidirectional"))
      (node (ref "JP10") (pin "23") (pinfunction "23_23") (pintype "passive"))
      (node (ref "JP2") (pin "23") (pinfunction "23_23") (pintype "passive"))
      (node (ref "R4") (pin "1") (pinfunction "1_1") (pintype "passive"))
      (node (ref "U$1") (pin "34-RX8") (pinfunction "34-RX8_34-RX8") (pintype "bidirectional"))
    )
    (net (code "36") (name "35") (class "Default")
      (node (ref "IC9") (pin "38") (pinfunction "~{CS}_38") (pintype "bidirectional"))
      (node (ref "JP10") (pin "22") (pinfunction "22_22") (pintype "passive"))
      (node (ref "JP2") (pin "22") (pinfunction "22_22") (pintype "passive"))
      (node (ref "R5") (pin "1") (pinfunction "1_1") (pintype "passive"))
      (node (ref "U$1") (pin "35-TX8") (pinfunction "35/TX8_35-TX8") (pintype "bidirectional"))
    )
    (net (code "37") (name "36") (class "Default")
      (node (ref "JP10") (pin "21") (pinfunction "21_21") (pintype "passive"))
      (node (ref "JP2") (pin "21") (pinfunction "21_21") (pintype "passive"))
      (node (ref "U$1") (pin "36-PWM") (pinfunction "36-PWM_36-PWM") (pintype "bidirectional"))
    )
    (net (code "38") (name "37") (class "Default")
      (node (ref "JP10") (pin "20") (pinfunction "20_20") (pintype "passive"))
      (node (ref "JP2") (pin "20") (pinfunction "20_20") (pintype "passive"))
      (node (ref "U$1") (pin "37-PWM") (pinfunction "37-PWM_37-PWM") (pintype "bidirectional"))
    )
    (net (code "39") (name "38") (class "Default")
      (node (ref "JP10") (pin "19") (pinfunction "19_19") (pintype "passive"))
      (node (ref "JP2") (pin "19") (pinfunction "19_19") (pintype "passive"))
      (node (ref "U$1") (pin "38-A14/CS/IN1") (pinfunction "38-A14/CS/IN1_38-A14/CS/IN1") (pintype "bidirectional"))
    )
    (net (code "40") (name "39") (class "Default")
      (node (ref "JP10") (pin "18") (pinfunction "18_18") (pintype "passive"))
      (node (ref "JP2") (pin "18") (pinfunction "18_18") (pintype "passive"))
      (node (ref "U$1") (pin "39-A15/CS/OUT1A") (pinfunction "39-A15/CS/OUT1A_39-A15/CS/OUT1A") (pintype "bidirectional"))
    )
    (net (code "41") (name "40") (class "Default")
      (node (ref "JP10") (pin "17") (pinfunction "17_17") (pintype "passive"))
      (node (ref "JP2") (pin "17") (pinfunction "17_17") (pintype "passive"))
      (node (ref "U$1") (pin "40-A16/CS1") (pinfunction "40-A16/CS1_40-A16/CS1") (pintype "bidirectional"))
    )
    (net (code "42") (name "41") (class "Default")
      (node (ref "JP10") (pin "16") (pinfunction "16_16") (pintype "passive"))
      (node (ref "JP2") (pin "16") (pinfunction "16_16") (pintype "passive"))
      (node (ref "U$1") (pin "41-A17/MISO1") (pinfunction "41-A17/MISO1_41-A17/MISO1") (pintype "bidirectional"))
    )
    (net (code "43") (name "ADC1") (class "Default")
      (node (ref "A0") (pin "P$2") (pinfunction "2_P$2") (pintype "passive"))
      (node (ref "IC7") (pin "16") (pinfunction "AIN_0P_16") (pintype "bidirectional"))
    )
    (net (code "44") (name "ADC2") (class "Default")
      (node (ref "A1") (pin "P$2") (pinfunction "2_P$2") (pintype "passive"))
      (node (ref "IC7") (pin "18") (pinfunction "AIN_1P_18") (pintype "bidirectional"))
    )
    (net (code "45") (name "ADC3") (class "Default")
      (node (ref "A2") (pin "P$2") (pinfunction "2_P$2") (pintype "passive"))
      (node (ref "IC7") (pin "21") (pinfunction "AIN_2P_21") (pintype "bidirectional"))
    )
    (net (code "46") (name "ADC4") (class "Default")
      (node (ref "A3") (pin "P$2") (pinfunction "2_P$2") (pintype "passive"))
      (node (ref "IC7") (pin "23") (pinfunction "AIN_3P_23") (pintype "bidirectional"))
    )
    (net (code "47") (name "ADC5") (class "Default")
      (node (ref "A4") (pin "P$2") (pinfunction "2_P$2") (pintype "passive"))
      (node (ref "IC7") (pin "25") (pinfunction "AIN_4P_25") (pintype "bidirectional"))
    )
    (net (code "48") (name "ADC6") (class "Default")
      (node (ref "A5") (pin "P$2") (pinfunction "2_P$2") (pintype "passive"))
      (node (ref "IC7") (pin "27") (pinfunction "AIN_5P_27") (pintype "bidirectional"))
    )
    (net (code "49") (name "ADC7") (class "Default")
      (node (ref "A6") (pin "P$2") (pinfunction "2_P$2") (pintype "passive"))
      (node (ref "IC7") (pin "12") (pinfunction "AIN_6P_12") (pintype "bidirectional"))
    )
    (net (code "50") (name "ADC8") (class "Default")
      (node (ref "A7") (pin "P$2") (pinfunction "2_P$2") (pintype "passive"))
      (node (ref "IC7") (pin "14") (pinfunction "AIN_7P_14") (pintype "bidirectional"))
    )
    (net (code "51") (name "ADC9") (class "Default")
      (node (ref "A8") (pin "P$2") (pinfunction "2_P$2") (pintype "passive"))
      (node (ref "IC8") (pin "16") (pinfunction "AIN_0P_16") (pintype "bidirectional"))
    )
    (net (code "52") (name "ADC10") (class "Default")
      (node (ref "A9") (pin "P$2") (pinfunction "2_P$2") (pintype "passive"))
      (node (ref "IC8") (pin "18") (pinfunction "AIN_1P_18") (pintype "bidirectional"))
    )
    (net (code "53") (name "ADC11") (class "Default")
      (node (ref "A10") (pin "P$2") (pinfunction "2_P$2") (pintype "passive"))
      (node (ref "IC8") (pin "21") (pinfunction "AIN_2P_21") (pintype "bidirectional"))
    )
    (net (code "54") (name "ADC12") (class "Default")
      (node (ref "A11") (pin "P$2") (pinfunction "2_P$2") (pintype "passive"))
      (node (ref "IC8") (pin "23") (pinfunction "AIN_3P_23") (pintype "bidirectional"))
    )
    (net (code "55") (name "ADC13") (class "Default")
      (node (ref "IC8") (pin "25") (pinfunction "AIN_4P_25") (pintype "bidirectional"))
      (node (ref "JP1") (pin "1") (pinfunction "1_1") (pintype "passive"))
    )
    (net (code "56") (name "ADC14") (class "Default")
      (node (ref "IC8") (pin "27") (pinfunction "AIN_5P_27") (pintype "bidirectional"))
      (node (ref "JP1") (pin "2") (pinfunction "2_2") (pintype "passive"))
    )
    (net (code "57") (name "ADC15") (class "Default")
      (node (ref "IC8") (pin "12") (pinfunction "AIN_6P_12") (pintype "bidirectional"))
      (node (ref "JP1") (pin "3") (pinfunction "3_3") (pintype "passive"))
    )
    (net (code "58") (name "ADC16") (class "Default")
      (node (ref "IC8") (pin "14") (pinfunction "AIN_7P_14") (pintype "bidirectional"))
      (node (ref "JP1") (pin "4") (pinfunction "4_4") (pintype "passive"))
    )
    (net (code "59") (name "ADC17") (class "Default")
      (node (ref "IC9") (pin "16") (pinfunction "AIN_0P_16") (pintype "bidirectional"))
      (node (ref "JP1") (pin "5") (pinfunction "5_5") (pintype "passive"))
    )
    (net (code "60") (name "ADC18") (class "Default")
      (node (ref "IC9") (pin "18") (pinfunction "AIN_1P_18") (pintype "bidirectional"))
      (node (ref "JP1") (pin "6") (pinfunction "6_6") (pintype "passive"))
    )
    (net (code "61") (name "ADC19") (class "Default")
      (node (ref "IC9") (pin "21") (pinfunction "AIN_2P_21") (pintype "bidirectional"))
      (node (ref "JP1") (pin "7") (pinfunction "7_7") (pintype "passive"))
    )
    (net (code "62") (name "ADC20") (class "Default")
      (node (ref "IC9") (pin "23") (pinfunction "AIN_3P_23") (pintype "bidirectional"))
      (node (ref "JP1") (pin "8") (pinfunction "8_8") (pintype "passive"))
    )
    (net (code "63") (name "ADC21") (class "Default")
      (node (ref "IC9") (pin "25") (pinfunction "AIN_4P_25") (pintype "bidirectional"))
      (node (ref "JP1") (pin "9") (pinfunction "9_9") (pintype "passive"))
    )
    (net (code "64") (name "ADC22") (class "Default")
      (node (ref "IC9") (pin "27") (pinfunction "AIN_5P_27") (pintype "bidirectional"))
      (node (ref "JP1") (pin "10") (pinfunction "10_10") (pintype "passive"))
    )
    (net (code "65") (name "ADC23") (class "Default")
      (node (ref "IC9") (pin "12") (pinfunction "AIN_6P_12") (pintype "bidirectional"))
      (node (ref "JP1") (pin "11") (pinfunction "11_11") (pintype "passive"))
    )
    (net (code "66") (name "ADC24") (class "Default")
      (node (ref "IC9") (pin "14") (pinfunction "AIN_7P_14") (pintype "bidirectional"))
      (node (ref "JP1") (pin "12") (pinfunction "12_12") (pintype "passive"))
    )
    (net (code "67") (name "D+") (class "Default")
      (node (ref "U$1") (pin "D+") (pinfunction "D+_D+") (pintype "bidirectional"))
    )
    (net (code "68") (name "D-") (class "Default")
      (node (ref "U$1") (pin "D-") (pinfunction "D-_D-") (pintype "bidirectional"))
    )
    (net (code "69") (name "DM") (class "Default")
      (node (ref "U$1") (pin "DM") (pinfunction "DM_DM") (pintype "bidirectional"))
    )
    (net (code "70") (name "DP") (class "Default")
      (node (ref "U$1") (pin "DP") (pinfunction "DP_DP") (pintype "bidirectional"))
    )
    (net (code "71") (name "G") (class "Default")
      (node (ref "U$1") (pin "G") (pinfunction "G_G") (pintype "bidirectional"))
    )
    (net (code "72") (name "GND") (class "Default")
      (node (ref "A0") (pin "P$3") (pinfunction "3_P$3") (pintype "passive"))
      (node (ref "A1") (pin "P$3") (pinfunction "3_P$3") (pintype "passive"))
      (node (ref "A10") (pin "P$3") (pinfunction "3_P$3") (pintype "passive"))
      (node (ref "A11") (pin "P$3") (pinfunction "3_P$3") (pintype "passive"))
      (node (ref "A2") (pin "P$3") (pinfunction "3_P$3") (pintype "passive"))
      (node (ref "A3") (pin "P$3") (pinfunction "3_P$3") (pintype "passive"))
      (node (ref "A4") (pin "P$3") (pinfunction "3_P$3") (pintype "passive"))
      (node (ref "A5") (pin "P$3") (pinfunction "3_P$3") (pintype "passive"))
      (node (ref "A6") (pin "P$3") (pinfunction "3_P$3") (pintype "passive"))
      (node (ref "A7") (pin "P$3") (pinfunction "3_P$3") (pintype "passive"))
      (node (ref "A8") (pin "P$3") (pinfunction "3_P$3") (pintype "passive"))
      (node (ref "A9") (pin "P$3") (pinfunction "3_P$3") (pintype "passive"))
      (node (ref "C1") (pin "2") (pinfunction "2_2") (pintype "passive"))
      (node (ref "C16") (pin "2") (pinfunction "2_2") (pintype "passive"))
      (node (ref "C17") (pin "2") (pinfunction "2_2") (pintype "passive"))
      (node (ref "C18") (pin "1") (pinfunction "1_1") (pintype "passive"))
      (node (ref "C2") (pin "2") (pinfunction "2_2") (pintype "passive"))
      (node (ref "C20") (pin "2") (pinfunction "2_2") (pintype "passive"))
      (node (ref "C21") (pin "1") (pinfunction "1_1") (pintype "passive"))
      (node (ref "C3") (pin "2") (pinfunction "2_2") (pintype "passive"))
      (node (ref "C39") (pin "2") (pinfunction "2_2") (pintype "passive"))
      (node (ref "C4") (pin "2") (pinfunction "2_2") (pintype "passive"))
      (node (ref "C40") (pin "2") (pinfunction "2_2") (pintype "passive"))
      (node (ref "C41") (pin "1") (pinfunction "1_1") (pintype "passive"))
      (node (ref "C42") (pin "2") (pinfunction "2_2") (pintype "passive"))
      (node (ref "C43") (pin "1") (pinfunction "1_1") (pintype "passive"))
      (node (ref "C44") (pin "1") (pinfunction "1_1") (pintype "passive"))
      (node (ref "C5") (pin "1") (pinfunction "1_1") (pintype "passive"))
      (node (ref "C54") (pin "2") (pinfunction "2_2") (pintype "passive"))
      (node (ref "C55") (pin "2") (pinfunction "2_2") (pintype "passive"))
      (node (ref "C56") (pin "1") (pinfunction "1_1") (pintype "passive"))
      (node (ref "C57") (pin "2") (pinfunction "2_2") (pintype "passive"))
      (node (ref "C58") (pin "1") (pinfunction "1_1") (pintype "passive"))
      (node (ref "C6") (pin "1") (pinfunction "1_1") (pintype "passive"))
      (node (ref "CS=10") (pin "P$6") (pinfunction "6_P$6") (pintype "passive"))
      (node (ref "CS=11") (pin "P$6") (pinfunction "6_P$6") (pintype "passive"))
      (node (ref "D1") (pin "P$3") (pinfunction "3_P$3") (pintype "passive"))
      (node (ref "D2") (pin "P$3") (pinfunction "3_P$3") (pintype "passive"))
      (node (ref "D3") (pin "P$3") (pinfunction "3_P$3") (pintype "passive"))
      (node (ref "D4") (pin "P$3") (pinfunction "3_P$3") (pintype "passive"))
      (node (ref "D5") (pin "P$3") (pinfunction "3_P$3") (pintype "passive"))
      (node (ref "D6") (pin "P$3") (pinfunction "3_P$3") (pintype "passive"))
      (node (ref "D7") (pin "P$3") (pinfunction "3_P$3") (pintype "passive"))
      (node (ref "D8") (pin "P$3") (pinfunction "3_P$3") (pintype "passive"))
      (node (ref "I2C1") (pin "P$4") (pinfunction "4_P$4") (pintype "passive"))
      (node (ref "I2C2") (pin "P$4") (pinfunction "4_P$4") (pintype "passive"))
      (node (ref "IC7") (pin "11") (pinfunction "AUX_GND_11") (pintype "bidirectional"))
      (node (ref "IC7") (pin "13") (pinfunction "AIN_6GND_13") (pintype "bidirectional"))
      (node (ref "IC7") (pin "15") (pinfunction "AIN_7GND_15") (pintype "bidirectional"))
      (node (ref "IC7") (pin "17") (pinfunction "AIN_0GND_17") (pintype "bidirectional"))
      (node (ref "IC7") (pin "19") (pinfunction "AIN_1GND_19") (pintype "bidirectional"))
      (node (ref "IC7") (pin "20") (pinfunction "AIN2_GND_20") (pintype "bidirectional"))
      (node (ref "IC7") (pin "22") (pinfunction "AIN_3GND_22") (pintype "bidirectional"))
      (node (ref "IC7") (pin "24") (pinfunction "AIN_4GND_24") (pintype "bidirectional"))
      (node (ref "IC7") (pin "26") (pinfunction "AIN_5GND_26") (pintype "bidirectional"))
      (node (ref "IC7") (pin "28") (pinfunction "AGND_2_28") (pintype "bidirectional"))
      (node (ref "IC7") (pin "29") (pinfunction "AGND_3_29") (pintype "bidirectional"))
      (node (ref "IC7") (pin "3") (pinfunction "DAISY_3") (pintype "bidirectional"))
      (node (ref "IC7") (pin "31") (pinfunction "AGND_4_31") (pintype "bidirectional"))
      (node (ref "IC7") (pin "32") (pinfunction "AGND_5_32") (pintype "bidirectional"))
      (node (ref "IC7") (pin "33") (pinfunction "DGND_33") (pintype "bidirectional"))
      (node (ref "IC7") (pin "4") (pinfunction "~{REFSEL}_4") (pintype "bidirectional"))
      (node (ref "IC7") (pin "6") (pinfunction "REFGND_6") (pintype "bidirectional"))
      (node (ref "IC7") (pin "8") (pinfunction "AGND_1_8") (pintype "bidirectional"))
      (node (ref "IC8") (pin "11") (pinfunction "AUX_GND_11") (pintype "bidirectional"))
      (node (ref "IC8") (pin "13") (pinfunction "AIN_6GND_13") (pintype "bidirectional"))
      (node (ref "IC8") (pin "15") (pinfunction "AIN_7GND_15") (pintype "bidirectional"))
      (node (ref "IC8") (pin "17") (pinfunction "AIN_0GND_17") (pintype "bidirectional"))
      (node (ref "IC8") (pin "19") (pinfunction "AIN_1GND_19") (pintype "bidirectional"))
      (node (ref "IC8") (pin "20") (pinfunction "AIN2_GND_20") (pintype "bidirectional"))
      (node (ref "IC8") (pin "22") (pinfunction "AIN_3GND_22") (pintype "bidirectional"))
      (node (ref "IC8") (pin "24") (pinfunction "AIN_4GND_24") (pintype "bidirectional"))
      (node (ref "IC8") (pin "26") (pinfunction "AIN_5GND_26") (pintype "bidirectional"))
      (node (ref "IC8") (pin "28") (pinfunction "AGND_2_28") (pintype "bidirectional"))
      (node (ref "IC8") (pin "29") (pinfunction "AGND_3_29") (pintype "bidirectional"))
      (node (ref "IC8") (pin "3") (pinfunction "DAISY_3") (pintype "bidirectional"))
      (node (ref "IC8") (pin "31") (pinfunction "AGND_4_31") (pintype "bidirectional"))
      (node (ref "IC8") (pin "32") (pinfunction "AGND_5_32") (pintype "bidirectional"))
      (node (ref "IC8") (pin "33") (pinfunction "DGND_33") (pintype "bidirectional"))
      (node (ref "IC8") (pin "4") (pinfunction "~{REFSEL}_4") (pintype "bidirectional"))
      (node (ref "IC8") (pin "6") (pinfunction "REFGND_6") (pintype "bidirectional"))
      (node (ref "IC8") (pin "8") (pinfunction "AGND_1_8") (pintype "bidirectional"))
      (node (ref "IC9") (pin "11") (pinfunction "AUX_GND_11") (pintype "bidirectional"))
      (node (ref "IC9") (pin "13") (pinfunction "AIN_6GND_13") (pintype "bidirectional"))
      (node (ref "IC9") (pin "15") (pinfunction "AIN_7GND_15") (pintype "bidirectional"))
      (node (ref "IC9") (pin "17") (pinfunction "AIN_0GND_17") (pintype "bidirectional"))
      (node (ref "IC9") (pin "19") (pinfunction "AIN_1GND_19") (pintype "bidirectional"))
      (node (ref "IC9") (pin "20") (pinfunction "AIN2_GND_20") (pintype "bidirectional"))
      (node (ref "IC9") (pin "22") (pinfunction "AIN_3GND_22") (pintype "bidirectional"))
      (node (ref "IC9") (pin "24") (pinfunction "AIN_4GND_24") (pintype "bidirectional"))
      (node (ref "IC9") (pin "26") (pinfunction "AIN_5GND_26") (pintype "bidirectional"))
      (node (ref "IC9") (pin "28") (pinfunction "AGND_2_28") (pintype "bidirectional"))
      (node (ref "IC9") (pin "29") (pinfunction "AGND_3_29") (pintype "bidirectional"))
      (node (ref "IC9") (pin "3") (pinfunction "DAISY_3") (pintype "bidirectional"))
      (node (ref "IC9") (pin "31") (pinfunction "AGND_4_31") (pintype "bidirectional"))
      (node (ref "IC9") (pin "32") (pinfunction "AGND_5_32") (pintype "bidirectional"))
      (node (ref "IC9") (pin "33") (pinfunction "DGND_33") (pintype "bidirectional"))
      (node (ref "IC9") (pin "4") (pinfunction "~{REFSEL}_4") (pintype "bidirectional"))
      (node (ref "IC9") (pin "6") (pinfunction "REFGND_6") (pintype "bidirectional"))
      (node (ref "IC9") (pin "8") (pinfunction "AGND_1_8") (pintype "bidirectional"))
      (node (ref "JP10") (pin "15") (pinfunction "15_15") (pintype "passive"))
      (node (ref "JP10") (pin "2") (pinfunction "2_2") (pintype "passive"))
      (node (ref "JP2") (pin "15") (pinfunction "15_15") (pintype "passive"))
      (node (ref "JP2") (pin "2") (pinfunction "2_2") (pintype "passive"))
      (node (ref "JP4") (pin "1") (pinfunction "1_1") (pintype "passive"))
      (node (ref "JP7") (pin "1") (pinfunction "1_1") (pintype "passive"))
      (node (ref "LED1") (pin "C") (pinfunction "C_C") (pintype "passive"))
      (node (ref "LED2") (pin "C") (pinfunction "C_C") (pintype "passive"))
      (node (ref "U$1") (pin "GND1") (pinfunction "GND1_GND1") (pintype "bidirectional"))
      (node (ref "U$1") (pin "GND2") (pinfunction "GND2_GND2") (pintype "bidirectional"))
      (node (ref "U$1") (pin "GND3") (pinfunction "GND3_GND3") (pintype "bidirectional"))
      (node (ref "U$1") (pin "GND6") (pinfunction "GND6_GND6") (pintype "bidirectional"))
      (node (ref "U$2") (pin "NEG") (pinfunction "NEG_NEG") (pintype "bidirectional"))
      (node (ref "U$3") (pin "1") (pinfunction "GND_1") (pintype "input"))
      (node (ref "U$4") (pin "1") (pinfunction "GND_1") (pintype "input"))
      (node (ref "U1") (pin "10") (pinfunction "GND_10") (pintype "power_in"))
    )
    (net (code "73") (name "LED") (class "Default")
      (node (ref "U$1") (pin "LED") (pinfunction "LED_LED") (pintype "bidirectional"))
    )
    (net (code "74") (name "MISO") (class "Default")
      (node (ref "CS=10") (pin "P$3") (pinfunction "3_P$3") (pintype "passive"))
      (node (ref "CS=11") (pin "P$3") (pinfunction "3_P$3") (pintype "passive"))
      (node (ref "IC7") (pin "36") (pinfunction "SDO_36") (pintype "bidirectional"))
      (node (ref "IC8") (pin "36") (pinfunction "SDO_36") (pintype "bidirectional"))
      (node (ref "IC9") (pin "36") (pinfunction "SDO_36") (pintype "bidirectional"))
      (node (ref "JP1") (pin "14") (pinfunction "14_14") (pintype "passive"))
      (node (ref "JP7") (pin "14") (pinfunction "14_14") (pintype "passive"))
      (node (ref "U$1") (pin "12-MISO/MQSL") (pinfunction "12-MISO/MQSL_12-MISO/MQSL") (pintype "bidirectional"))
    )
    (net (code "75") (name "MOSI") (class "Default")
      (node (ref "CS=10") (pin "P$2") (pinfunction "2_P$2") (pintype "passive"))
      (node (ref "CS=11") (pin "P$2") (pinfunction "2_P$2") (pintype "passive"))
      (node (ref "IC7") (pin "1") (pinfunction "SDI_1") (pintype "bidirectional"))
      (node (ref "IC8") (pin "1") (pinfunction "SDI_1") (pintype "bidirectional"))
      (node (ref "IC9") (pin "1") (pinfunction "SDI_1") (pintype "bidirectional"))
      (node (ref "JP1") (pin "13") (pinfunction "13_13") (pintype "passive"))
      (node (ref "JP7") (pin "13") (pinfunction "13_13") (pintype "passive"))
      (node (ref "U$1") (pin "11-MOSI/CTX1") (pinfunction "11-MOSI/CTX1_11-MOSI/CTX1") (pintype "bidirectional"))
    )
    (net (code "76") (name "NC1") (class "Default")
      (node (ref "IC7") (pin "35") (pinfunction "DNC_35") (pintype "bidirectional"))
    )
    (net (code "77") (name "NC2") (class "Default")
      (node (ref "IC8") (pin "35") (pinfunction "DNC_35") (pintype "bidirectional"))
    )
    (net (code "78") (name "NC3") (class "Default")
      (node (ref "IC9") (pin "35") (pinfunction "DNC_35") (pintype "bidirectional"))
    )
    (net (code "79") (name "Net-(IC7-REFCAP)") (class "Default")
      (node (ref "C18") (pin "2") (pinfunction "2_2") (pintype "passive"))
      (node (ref "C21") (pin "2") (pinfunction "2_2") (pintype "passive"))
      (node (ref "IC7") (pin "7") (pinfunction "REFCAP_7") (pintype "bidirectional"))
    )
    (net (code "80") (name "Net-(IC7-REFIO)") (class "Default")
      (node (ref "C20") (pin "1") (pinfunction "1_1") (pintype "passive"))
      (node (ref "IC7") (pin "5") (pinfunction "REFIO_5") (pintype "bidirectional"))
    )
    (net (code "81") (name "Net-(IC8-REFCAP)") (class "Default")
      (node (ref "C41") (pin "2") (pinfunction "2_2") (pintype "passive"))
      (node (ref "C43") (pin "2") (pinfunction "2_2") (pintype "passive"))
      (node (ref "IC8") (pin "7") (pinfunction "REFCAP_7") (pintype "bidirectional"))
    )
    (net (code "82") (name "Net-(IC8-REFIO)") (class "Default")
      (node (ref "C42") (pin "1") (pinfunction "1_1") (pintype "passive"))
      (node (ref "IC8") (pin "5") (pinfunction "REFIO_5") (pintype "bidirectional"))
    )
    (net (code "83") (name "Net-(IC9-REFCAP)") (class "Default")
      (node (ref "C56") (pin "2") (pinfunction "2_2") (pintype "passive"))
      (node (ref "C58") (pin "2") (pinfunction "2_2") (pintype "passive"))
      (node (ref "IC9") (pin "7") (pinfunction "REFCAP_7") (pintype "bidirectional"))
    )
    (net (code "84") (name "Net-(IC9-REFIO)") (class "Default")
      (node (ref "C57") (pin "1") (pinfunction "1_1") (pintype "passive"))
      (node (ref "IC9") (pin "5") (pinfunction "REFIO_5") (pintype "bidirectional"))
    )
    (net (code "85") (name "Net-(LED1-PadA)") (class "Default")
      (node (ref "LED1") (pin "A") (pinfunction "A_A") (pintype "passive"))
      (node (ref "R1") (pin "2") (pinfunction "2_2") (pintype "passive"))
    )
    (net (code "86") (name "Net-(LED2-PadA)") (class "Default")
      (node (ref "LED2") (pin "A") (pinfunction "A_A") (pintype "passive"))
      (node (ref "R2") (pin "2") (pinfunction "2_2") (pintype "passive"))
    )
    (net (code "87") (name "PROGRAM") (class "Default")
      (node (ref "U$1") (pin "PROGRAM") (pinfunction "PROGRAM_PROGRAM") (pintype "bidirectional"))
    )
    (net (code "88") (name "R+") (class "Default")
      (node (ref "U$1") (pin "R+") (pinfunction "R+_R+") (pintype "bidirectional"))
    )
    (net (code "89") (name "R-") (class "Default")
      (node (ref "U$1") (pin "R-") (pinfunction "R-_R-") (pintype "bidirectional"))
    )
    (net (code "90") (name "SCK") (class "Default")
      (node (ref "CS=10") (pin "P$4") (pinfunction "4_P$4") (pintype "passive"))
      (node (ref "CS=11") (pin "P$4") (pinfunction "4_P$4") (pintype "passive"))
      (node (ref "IC7") (pin "37") (pinfunction "SCLK_37") (pintype "bidirectional"))
      (node (ref "IC8") (pin "37") (pinfunction "SCLK_37") (pintype "bidirectional"))
      (node (ref "IC9") (pin "37") (pinfunction "SCLK_37") (pintype "bidirectional"))
      (node (ref "JP10") (pin "14") (pinfunction "14_14") (pintype "passive"))
      (node (ref "JP2") (pin "14") (pinfunction "14_14") (pintype "passive"))
      (node (ref "U$1") (pin "13-SCK/LED") (pinfunction "13-SCK/LED_13-SCK/LED") (pintype "bidirectional"))
    )
    (net (code "91") (name "SCL") (class "Default")
      (node (ref "I2C1") (pin "P$3") (pinfunction "3_P$3") (pintype "passive"))
      (node (ref "I2C2") (pin "P$3") (pinfunction "3_P$3") (pintype "passive"))
      (node (ref "JP10") (pin "8") (pinfunction "8_8") (pintype "passive"))
      (node (ref "JP2") (pin "8") (pinfunction "8_8") (pintype "passive"))
      (node (ref "U$1") (pin "19-A5/SCL0") (pinfunction "19-A5/SCL0_19-A5/SCL0") (pintype "bidirectional"))
    )
    (net (code "92") (name "SDA") (class "Default")
      (node (ref "I2C1") (pin "P$2") (pinfunction "2_P$2") (pintype "passive"))
      (node (ref "I2C2") (pin "P$2") (pinfunction "2_P$2") (pintype "passive"))
      (node (ref "JP10") (pin "9") (pinfunction "9_9") (pintype "passive"))
      (node (ref "JP2") (pin "9") (pinfunction "9_9") (pintype "passive"))
      (node (ref "U$1") (pin "18-A4/SDA0") (pinfunction "18-A4/SDA0_18-A4/SDA0") (pintype "bidirectional"))
    )
    (net (code "93") (name "T+") (class "Default")
      (node (ref "U$1") (pin "T+") (pinfunction "T+_T+") (pintype "bidirectional"))
    )
    (net (code "94") (name "T-") (class "Default")
      (node (ref "U$1") (pin "T-") (pinfunction "T-_T-") (pintype "bidirectional"))
    )
    (net (code "95") (name "VBAT") (class "Default")
      (node (ref "U$1") (pin "VBAT") (pinfunction "VBAT_VBAT") (pintype "bidirectional"))
      (node (ref "U$2") (pin "VCC1") (pinfunction "VCC1_VCC1") (pintype "bidirectional"))
      (node (ref "U$2") (pin "VCC2") (pinfunction "VCC2_VCC2") (pintype "bidirectional"))
    )
    (net (code "96") (name "VUSB") (class "Default")
      (node (ref "U$1") (pin "VUSB") (pinfunction "VUSB_VUSB") (pintype "bidirectional"))
    )
    (net (code "97") (name "XBEE_DIN") (class "Default")
      (node (ref "JP7") (pin "3") (pinfunction "3_3") (pintype "passive"))
      (node (ref "U$1") (pin "1-TX1/MISO1/CTX2") (pinfunction "1-TX1/MISO1/CTX2_1-TX1/MISO1/CTX2") (pintype "bidirectional"))
      (node (ref "U1") (pin "3") (pinfunction "DIN/NCONFIG/DIO14_3") (pintype "bidirectional"))
    )
    (net (code "98") (name "XBEE_DOUT") (class "Default")
      (node (ref "JP7") (pin "2") (pinfunction "2_2") (pintype "passive"))
      (node (ref "U$1") (pin "0-RX1/CS1/CRX2") (pinfunction "0-RX1/CS1/CRX2_0-RX1/CS1/CRX2") (pintype "bidirectional"))
      (node (ref "U1") (pin "2") (pinfunction "DOUT/DIO13_2") (pintype "bidirectional"))
    )
    (net (code "99") (name "unconnected-(IC7-AUX_IN-Pad10)") (class "Default")
      (node (ref "IC7") (pin "10") (pinfunction "AUX_IN_10") (pintype "bidirectional"))
    )
    (net (code "100") (name "unconnected-(IC8-AUX_IN-Pad10)") (class "Default")
      (node (ref "IC8") (pin "10") (pinfunction "AUX_IN_10") (pintype "bidirectional"))
    )
    (net (code "101") (name "unconnected-(IC9-AUX_IN-Pad10)") (class "Default")
      (node (ref "IC9") (pin "10") (pinfunction "AUX_IN_10") (pintype "bidirectional"))
    )
    (net (code "102") (name "unconnected-(U$1-PadGND4)") (class "Default")
      (node (ref "U$1") (pin "GND4") (pinfunction "GND4_GND4") (pintype "bidirectional"))
    )
    (net (code "103") (name "unconnected-(U$1-PadGND5)") (class "Default")
      (node (ref "U$1") (pin "GND5") (pinfunction "GND5_GND5") (pintype "bidirectional"))
    )
    (net (code "104") (name "unconnected-(U$1-PadON{slash}OFF)") (class "Default")
      (node (ref "U$1") (pin "ON/OFF") (pinfunction "ON/OFF_ON/OFF") (pintype "bidirectional"))
    )
    (net (code "105") (name "unconnected-(U1-AD0{slash}DIO0-Pad20)") (class "Default")
      (node (ref "U1") (pin "20") (pinfunction "AD0/DIO0_20") (pintype "bidirectional"))
    )
    (net (code "106") (name "unconnected-(U1-AD1{slash}DIO1{slash}SPI_NATTN-Pad19)") (class "Default")
      (node (ref "U1") (pin "19") (pinfunction "AD1/DIO1/SPI_NATTN_19") (pintype "bidirectional"))
    )
    (net (code "107") (name "unconnected-(U1-AD2{slash}DIO2{slash}SPI_CLK-Pad18)") (class "Default")
      (node (ref "U1") (pin "18") (pinfunction "AD2/DIO2/SPI_CLK_18") (pintype "bidirectional"))
    )
    (net (code "108") (name "unconnected-(U1-AD3{slash}DIO3{slash}SPI_NSSEL-Pad17)") (class "Default")
      (node (ref "U1") (pin "17") (pinfunction "AD3/DIO3/SPI_NSSEL_17") (pintype "bidirectional"))
    )
    (net (code "109") (name "unconnected-(U1-ASSOCIATE{slash}DIO5-Pad15)") (class "Default")
      (node (ref "U1") (pin "15") (pinfunction "ASSOCIATE/DIO5_15") (pintype "output"))
    )
    (net (code "110") (name "unconnected-(U1-DIO4{slash}SPI_MOSI-Pad11)") (class "Default")
      (node (ref "U1") (pin "11") (pinfunction "DIO4/SPI_MOSI_11") (pintype "bidirectional"))
    )
    (net (code "111") (name "unconnected-(U1-DIO10{slash}PWM0-Pad6)") (class "Default")
      (node (ref "U1") (pin "6") (pinfunction "DIO10/PWM0_6") (pintype "bidirectional"))
    )
    (net (code "112") (name "unconnected-(U1-DIO11{slash}PWM1-Pad7)") (class "Default")
      (node (ref "U1") (pin "7") (pinfunction "DIO11/PWM1_7") (pintype "bidirectional"))
    )
    (net (code "113") (name "unconnected-(U1-DIO12{slash}SPI_MISO-Pad4)") (class "Default")
      (node (ref "U1") (pin "4") (pinfunction "DIO12/SPI_MISO_4") (pintype "bidirectional"))
    )
    (net (code "114") (name "unconnected-(U1-NCTS{slash}DIO7-Pad12)") (class "Default")
      (node (ref "U1") (pin "12") (pinfunction "NCTS/DIO7_12") (pintype "bidirectional"))
    )
    (net (code "115") (name "unconnected-(U1-NDTR{slash}SLEEP_RQ{slash}DIO8-Pad9)") (class "Default")
      (node (ref "U1") (pin "9") (pinfunction "NDTR/SLEEP_RQ/DIO8_9") (pintype "bidirectional"))
    )
    (net (code "116") (name "unconnected-(U1-NRTS{slash}DIO6-Pad16)") (class "Default")
      (node (ref "U1") (pin "16") (pinfunction "NRTS/DIO6_16") (pintype "input"))
    )
    (net (code "117") (name "unconnected-(U1-ON_NSLEEP{slash}DIO9-Pad13)") (class "Default")
      (node (ref "U1") (pin "13") (pinfunction "ON_NSLEEP/DIO9_13") (pintype "bidirectional"))
    )
    (net (code "118") (name "unconnected-(U1-VREF-Pad14)") (class "Default")
      (node (ref "U1") (pin "14") (pinfunction "VREF_14") (pintype "input"))
    )
    (net (code "119") (name "unconnected-(U1-~{RESET}-Pad5)") (class "Default")
      (node (ref "U1") (pin "5") (pinfunction "~{RESET}_5") (pintype "input"))
    )
  )
)
